# oledBreakout.net
KiCad netlist of a schematic drawn in EAGLE
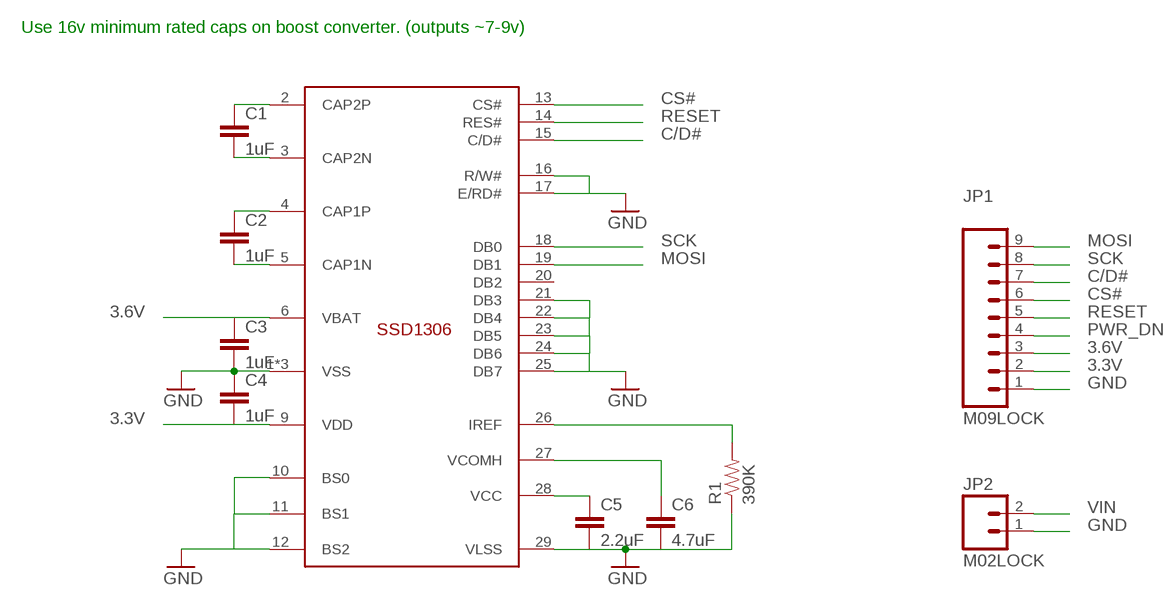
[diagram p0: schematic, sheet 1]

(export (version "E")
  (design (tool "Eeschema 10.0.6"))
  (components
    (comp (ref "C1")
      (value "1uF")
      (footprint "eagle-import:0402-CAP")
      (libsource (lib "eagle-import") (part "CAP0402-CAP"))
    )
    (comp (ref "C2")
      (value "1uF")
      (footprint "eagle-import:0402-CAP")
      (libsource (lib "eagle-import") (part "CAP0402-CAP"))
    )
    (comp (ref "C3")
      (value "1uF")
      (footprint "eagle-import:0402-CAP")
      (libsource (lib "eagle-import") (part "CAP0402-CAP"))
    )
    (comp (ref "C4")
      (value "1uF")
      (footprint "eagle-import:0402-CAP")
      (libsource (lib "eagle-import") (part "CAP0402-CAP"))
    )
    (comp (ref "C5")
      (value "2.2uF")
      (footprint "eagle-import:0402-CAP")
      (libsource (lib "eagle-import") (part "CAP0402-CAP"))
    )
    (comp (ref "C6")
      (value "4.7uF")
      (footprint "eagle-import:0402-CAP")
      (libsource (lib "eagle-import") (part "CAP0402-CAP"))
    )
    (comp (ref "JP1")
      (value "M09LOCK")
      (footprint "eagle-import:1X09_LOCK")
      (libsource (lib "eagle-import") (part "M09LOCK"))
    )
    (comp (ref "JP2")
      (value "M02LOCK")
      (footprint "eagle-import:1X02_LOCK")
      (libsource (lib "eagle-import") (part "M02LOCK"))
    )
    (comp (ref "R1")
      (value "390K")
      (footprint "eagle-import:0402-RES")
      (libsource (lib "eagle-import") (part "RESISTOR0402-RES"))
    )
    (comp (ref "U$1")
      (value "ER-OLED0.96-2")
      (footprint "eagle-import:ER-OLED0.96-2")
      (libsource (lib "eagle-import") (part "ER-OLED0.96-2"))
    )
  )
  (nets
    (net (code "1") (name "/3.3V") (class "Default")
      (node (ref "C4") (pin "2") (pinfunction "2_2") (pintype "passive"))
      (node (ref "JP1") (pin "2") (pinfunction "2_2") (pintype "passive"))
      (node (ref "U$1") (pin "9") (pinfunction "VDD_9") (pintype "power_in"))
    )
    (net (code "2") (name "/3.6V") (class "Default")
      (node (ref "C3") (pin "1") (pinfunction "1_1") (pintype "passive"))
      (node (ref "JP1") (pin "3") (pinfunction "3_3") (pintype "passive"))
      (node (ref "U$1") (pin "6") (pinfunction "VBAT_6") (pintype "power_in"))
    )
    (net (code "3") (name "/CS#") (class "Default")
      (node (ref "JP1") (pin "6") (pinfunction "6_6") (pintype "passive"))
      (node (ref "U$1") (pin "13") (pinfunction "CS#_13") (pintype "bidirectional"))
    )
    (net (code "4") (name "/C{slash}D#") (class "Default")
      (node (ref "JP1") (pin "7") (pinfunction "7_7") (pintype "passive"))
      (node (ref "U$1") (pin "15") (pinfunction "C/D#_15") (pintype "bidirectional"))
    )
    (net (code "5") (name "/MOSI") (class "Default")
      (node (ref "JP1") (pin "9") (pinfunction "9_9") (pintype "passive"))
      (node (ref "U$1") (pin "19") (pinfunction "DB1_19") (pintype "bidirectional"))
    )
    (net (code "6") (name "/PWR_DN") (class "Default")
      (node (ref "JP1") (pin "4") (pinfunction "4_4") (pintype "passive"))
    )
    (net (code "7") (name "/RESET") (class "Default")
      (node (ref "JP1") (pin "5") (pinfunction "5_5") (pintype "passive"))
      (node (ref "U$1") (pin "14") (pinfunction "RES#_14") (pintype "bidirectional"))
    )
    (net (code "8") (name "/SCK") (class "Default")
      (node (ref "JP1") (pin "8") (pinfunction "8_8") (pintype "passive"))
      (node (ref "U$1") (pin "18") (pinfunction "DB0_18") (pintype "bidirectional"))
    )
    (net (code "9") (name "/VIN") (class "Default")
      (node (ref "JP2") (pin "2") (pinfunction "2_2") (pintype "passive"))
    )
    (net (code "10") (name "GND") (class "Default")
      (node (ref "C3") (pin "2") (pinfunction "2_2") (pintype "passive"))
      (node (ref "C4") (pin "1") (pinfunction "1_1") (pintype "passive"))
      (node (ref "C5") (pin "2") (pinfunction "2_2") (pintype "passive"))
      (node (ref "C6") (pin "2") (pinfunction "2_2") (pintype "passive"))
      (node (ref "JP1") (pin "1") (pinfunction "1_1") (pintype "passive"))
      (node (ref "JP2") (pin "1") (pinfunction "1_1") (pintype "passive"))
      (node (ref "R1") (pin "1") (pinfunction "1_1") (pintype "passive"))
      (node (ref "U$1") (pin "1") (pinfunction "VSS_1") (pintype "power_in"))
      (node (ref "U$1") (pin "10") (pinfunction "BS0_10") (pintype "bidirectional"))
      (node (ref "U$1") (pin "11") (pinfunction "BS1_11") (pintype "bidirectional"))
      (node (ref "U$1") (pin "12") (pinfunction "BS2_12") (pintype "bidirectional"))
      (node (ref "U$1") (pin "16") (pinfunction "R/W#_16") (pintype "bidirectional"))
      (node (ref "U$1") (pin "17") (pinfunction "E/RD#_17") (pintype "bidirectional"))
      (node (ref "U$1") (pin "21") (pinfunction "DB3_21") (pintype "bidirectional"))
      (node (ref "U$1") (pin "22") (pinfunction "DB4_22") (pintype "bidirectional"))
      (node (ref "U$1") (pin "23") (pinfunction "DB5_23") (pintype "bidirectional"))
      (node (ref "U$1") (pin "24") (pinfunction "DB6_24") (pintype "bidirectional"))
      (node (ref "U$1") (pin "25") (pinfunction "DB7_25") (pintype "bidirectional"))
      (node (ref "U$1") (pin "29") (pinfunction "VLSS_29") (pintype "power_in"))
      (node (ref "U$1") (pin "30") (pinfunction "VSS_30") (pintype "power_in"))
      (node (ref "U$1") (pin "8") (pinfunction "VSS_8") (pintype "power_in"))
    )
    (net (code "11") (name "Net-(U$1-CAP1N)") (class "Default")
      (node (ref "C2") (pin "2") (pinfunction "2_2") (pintype "passive"))
      (node (ref "U$1") (pin "5") (pinfunction "CAP1N_5") (pintype "power_in"))
    )
    (net (code "12") (name "Net-(U$1-CAP1P)") (class "Default")
      (node (ref "C2") (pin "1") (pinfunction "1_1") (pintype "passive"))
      (node (ref "U$1") (pin "4") (pinfunction "CAP1P_4") (pintype "power_in"))
    )
    (net (code "13") (name "Net-(U$1-CAP2N)") (class "Default")
      (node (ref "C1") (pin "2") (pinfunction "2_2") (pintype "passive"))
      (node (ref "U$1") (pin "3") (pinfunction "CAP2N_3") (pintype "power_in"))
    )
    (net (code "14") (name "Net-(U$1-CAP2P)") (class "Default")
      (node (ref "C1") (pin "1") (pinfunction "1_1") (pintype "passive"))
      (node (ref "U$1") (pin "2") (pinfunction "CAP2P_2") (pintype "power_in"))
    )
    (net (code "15") (name "Net-(U$1-IREF)") (class "Default")
      (node (ref "R1") (pin "2") (pinfunction "2_2") (pintype "passive"))
      (node (ref "U$1") (pin "26") (pinfunction "IREF_26") (pintype "power_in"))
    )
    (net (code "16") (name "Net-(U$1-VCC)") (class "Default")
      (node (ref "C5") (pin "1") (pinfunction "1_1") (pintype "passive"))
      (node (ref "U$1") (pin "28") (pinfunction "VCC_28") (pintype "power_in"))
    )
    (net (code "17") (name "Net-(U$1-VCOMH)") (class "Default")
      (node (ref "C6") (pin "1") (pinfunction "1_1") (pintype "passive"))
      (node (ref "U$1") (pin "27") (pinfunction "VCOMH_27") (pintype "power_in"))
    )
    (net (code "18") (name "unconnected-(U$1-DB2-Pad20)") (class "Default")
      (node (ref "U$1") (pin "20") (pinfunction "DB2_20") (pintype "bidirectional"))
    )
  )
)
